# SCH_ESP_Hisense_485_2022-09-16.net
KiCad netlist of a schematic drawn in EasyEDA
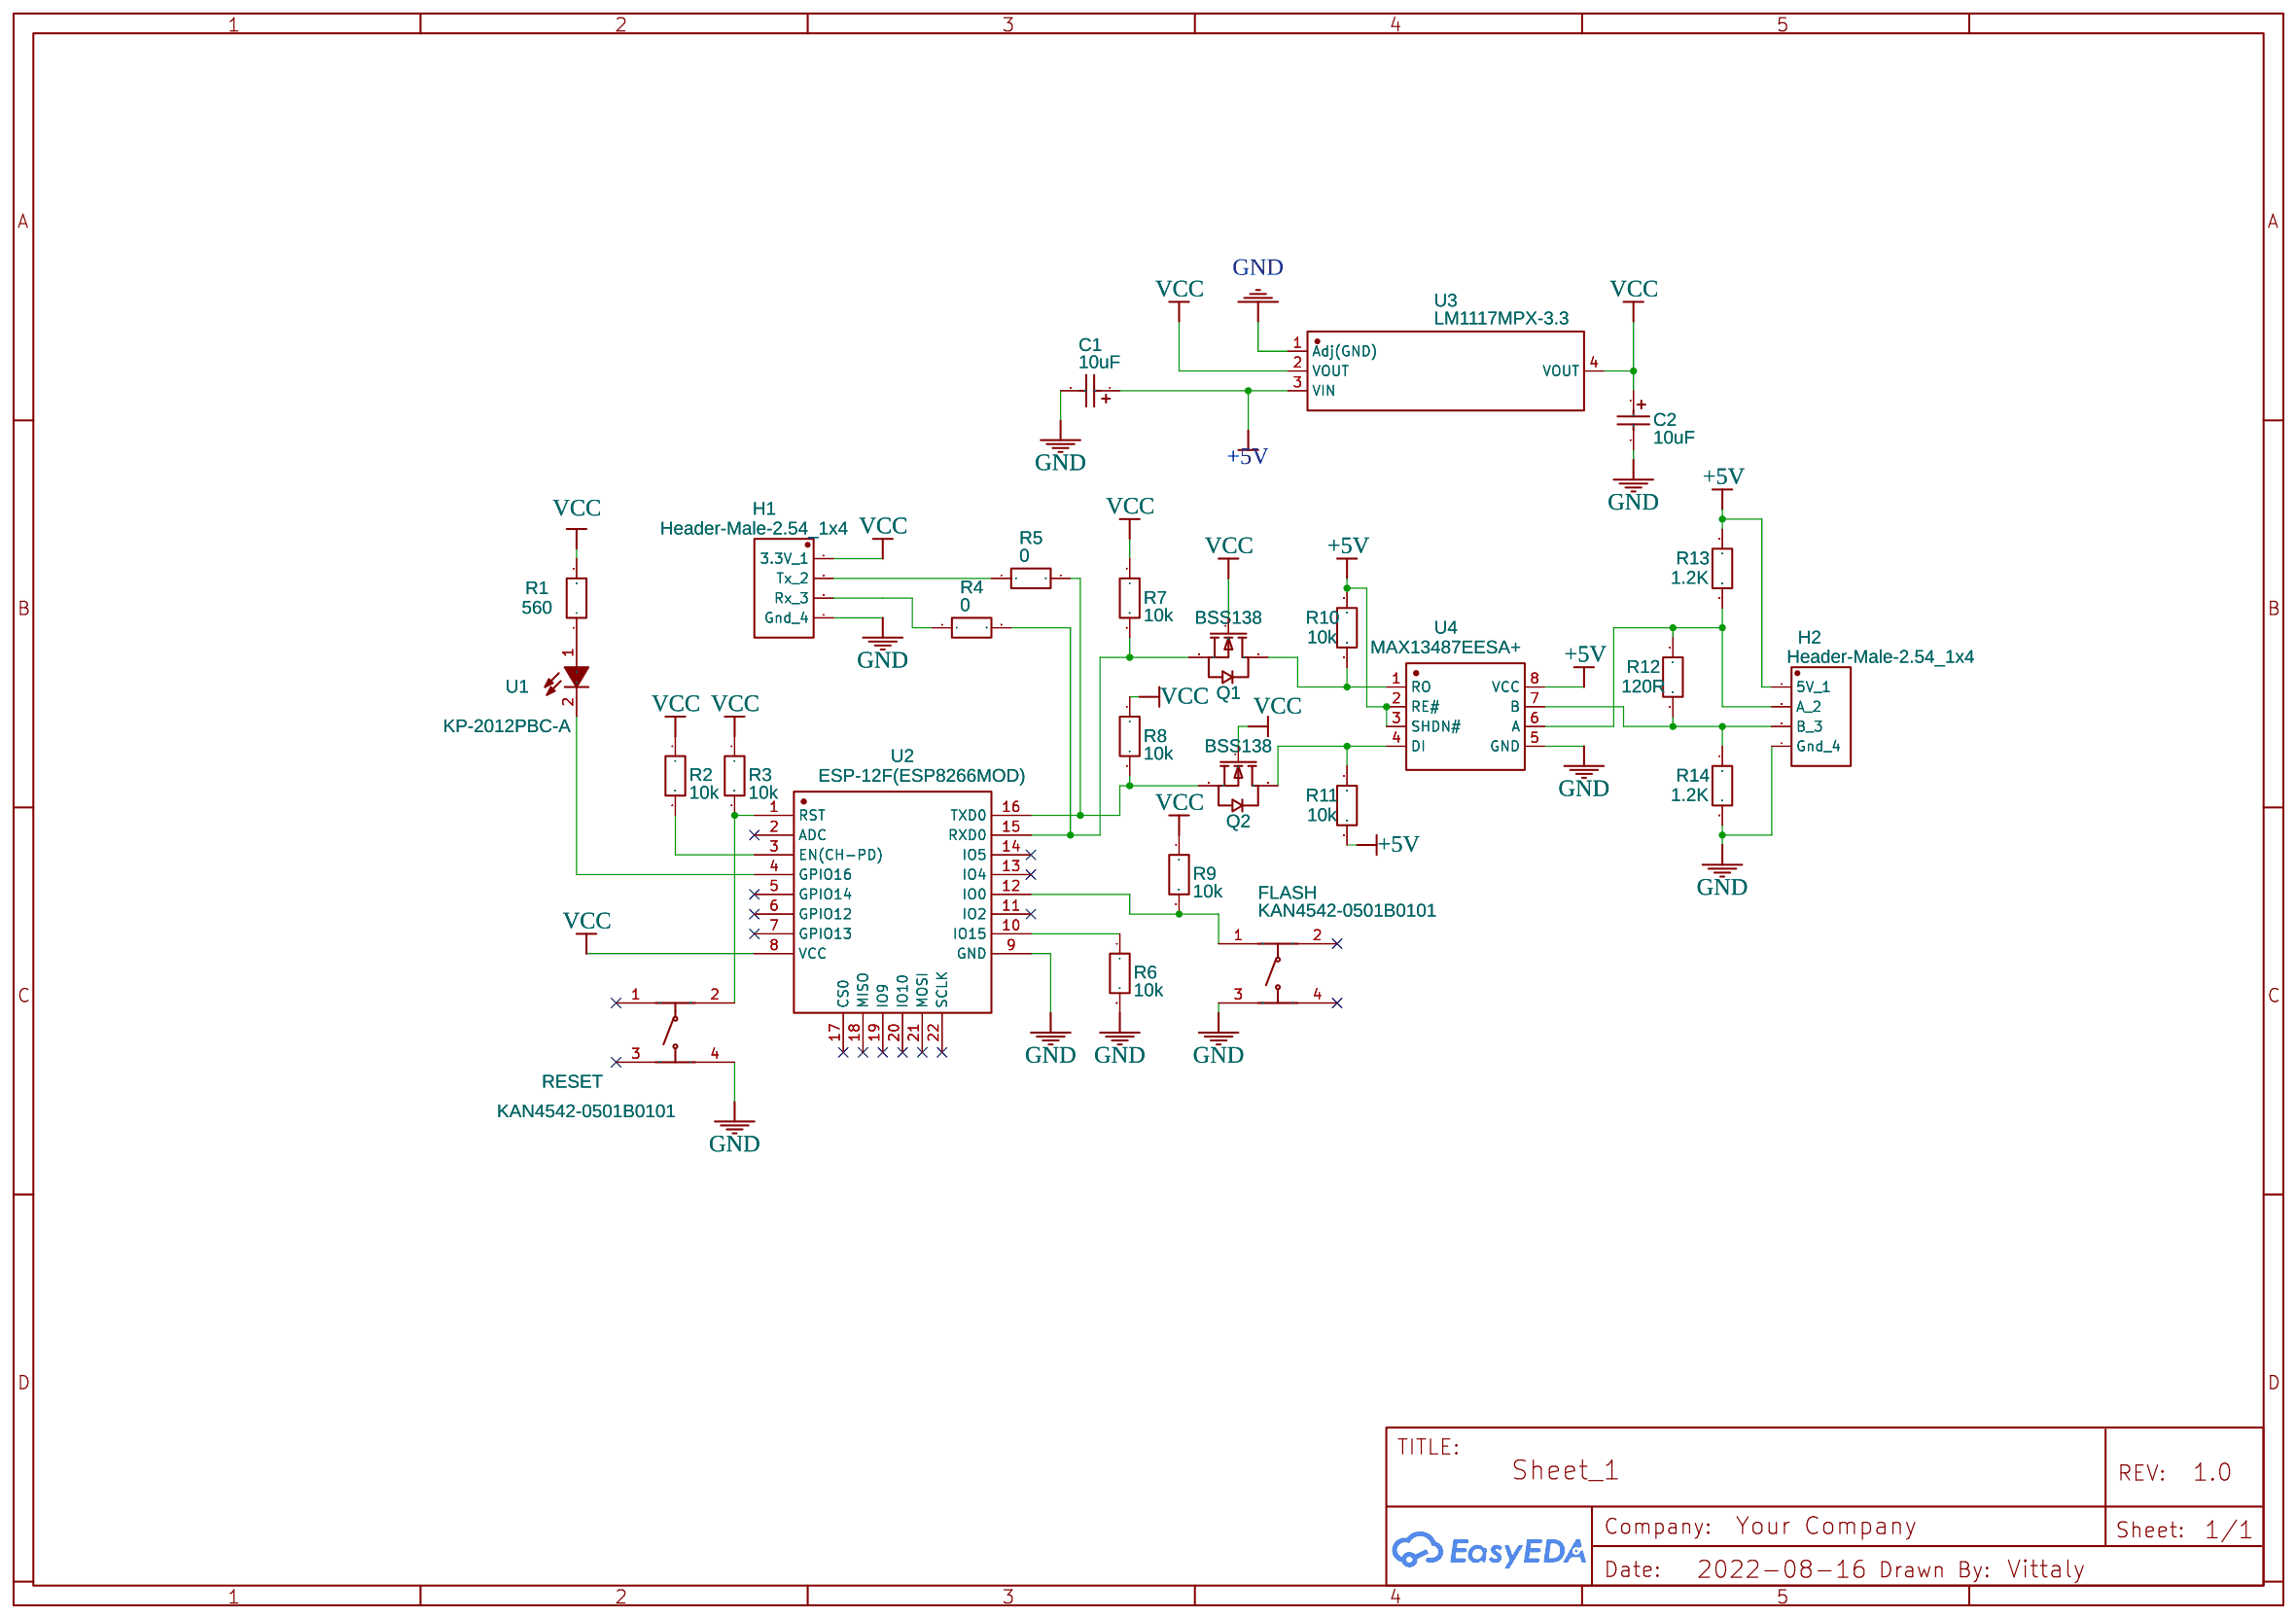
[diagram p0: schematic sheet]

(export (version "E")
  (design (tool "Eeschema 10.0.6"))
  (components
    (comp (ref "C1")
      (value "10uF")
      (fields
        (field (name "BOM_Manufacturer Part") "TAJB106M016RNJ")
        (field (name "BOM_Supplier Part") "C8016")
      )
      (libsource (lib "") (part "TAJB106M016RNJ"))
    )
    (comp (ref "C2")
      (value "10uF")
      (fields
        (field (name "BOM_Manufacturer Part") "TAJB106M016RNJ")
        (field (name "BOM_Supplier Part") "C8016")
      )
      (libsource (lib "") (part "TAJB106M016RNJ_1"))
    )
    (comp (ref "FLASH")
      (value "KAN4542-0501B0101")
      (fields (field (name "BOM_Supplier Part") "C2831431"))
      (libsource (lib "") (part "KAN4542-0501B0101_1"))
    )
    (comp (ref "H1")
      (value "Header-Male-2.54_1x4")
      (fields
        (field (name "BOM_Manufacturer Part") "210S-1*4P L=11.6MMGold-plated black")
        (field (name "BOM_Supplier Part") "C124378")
      )
      (libsource (lib "") (part "Header-Male-2.54_1x4"))
    )
    (comp (ref "H2")
      (value "Header-Male-2.54_1x4")
      (fields
        (field (name "BOM_Manufacturer Part") "210S-1*4P L=11.6MMGold-plated black")
        (field (name "BOM_Supplier Part") "C124378")
      )
      (libsource (lib "") (part "Header-Male-2.54_1x4_1"))
    )
    (comp (ref "Q1")
      (value "BSS138")
      (fields (field (name "BOM_Supplier Part") "C2681829"))
      (libsource (lib "") (part "BSS138_C2681829"))
    )
    (comp (ref "Q2")
      (value "BSS138")
      (fields (field (name "BOM_Supplier Part") "C2681829"))
      (libsource (lib "") (part "BSS138_C2681829"))
    )
    (comp (ref "R1") (value "560") (libsource (lib "") (part "R_1206_EU_2")))
    (comp (ref "R2") (value "10k") (libsource (lib "") (part "R_1206_EU")))
    (comp (ref "R3") (value "10k") (libsource (lib "") (part "R_1206_EU")))
    (comp (ref "R4")
      (value "0")
      (fields
        (field (name "BOM_Manufacturer Part") "AC1206JR-071KL")
        (field (name "BOM_Supplier Part") "C138242")
      )
      (libsource (lib "") (part "R_1206_EU_1"))
    )
    (comp (ref "R5")
      (value "0")
      (fields
        (field (name "BOM_Manufacturer Part") "AC1206JR-071KL")
        (field (name "BOM_Supplier Part") "C138242")
      )
      (libsource (lib "") (part "R_1206_EU_1"))
    )
    (comp (ref "R6") (value "10k") (libsource (lib "") (part "R_1206_EU")))
    (comp (ref "R7")
      (value "10k")
      (fields
        (field (name "BOM_Manufacturer Part") "AC1206JR-071KL")
        (field (name "BOM_Supplier Part") "C138242")
      )
      (libsource (lib "") (part "R_1206_EU"))
    )
    (comp (ref "R8")
      (value "10k")
      (fields
        (field (name "BOM_Manufacturer Part") "AC1206JR-071KL")
        (field (name "BOM_Supplier Part") "C138242")
      )
      (libsource (lib "") (part "R_1206_EU"))
    )
    (comp (ref "R9") (value "10k") (libsource (lib "") (part "R_1206_EU")))
    (comp (ref "R10")
      (value "10k")
      (fields
        (field (name "BOM_Manufacturer Part") "AC1206JR-071KL")
        (field (name "BOM_Supplier Part") "C138242")
      )
      (libsource (lib "") (part "R_1206_EU"))
    )
    (comp (ref "R11")
      (value "10k")
      (fields
        (field (name "BOM_Manufacturer Part") "AC1206JR-071KL")
        (field (name "BOM_Supplier Part") "C138242")
      )
      (libsource (lib "") (part "R_1206_EU"))
    )
    (comp (ref "R12")
      (value "120R")
      (fields
        (field (name "BOM_Manufacturer Part") "AC1206JR-071KL")
        (field (name "BOM_Supplier Part") "C138242")
      )
      (libsource (lib "") (part "R_1206_EU"))
    )
    (comp (ref "R13")
      (value "1.2K")
      (fields
        (field (name "BOM_Manufacturer Part") "AC1206JR-071KL")
        (field (name "BOM_Supplier Part") "C138242")
      )
      (libsource (lib "") (part "R_1206_EU"))
    )
    (comp (ref "R14")
      (value "1.2K")
      (fields
        (field (name "BOM_Manufacturer Part") "AC1206JR-071KL")
        (field (name "BOM_Supplier Part") "C138242")
      )
      (libsource (lib "") (part "R_1206_EU"))
    )
    (comp (ref "RESET")
      (value "KAN4542-0501B0101")
      (fields (field (name "BOM_Supplier Part") "C2831431"))
      (libsource (lib "") (part "KAN4542-0501B0101"))
    )
    (comp (ref "U1")
      (value "KP-2012PBC-A")
      (fields (field (name "BOM_Supplier Part") "C598276"))
      (libsource (lib "") (part "KP-2012PBC-A"))
    )
    (comp (ref "U2")
      (value "ESP-12F(ESP8266MOD)")
      (fields (field (name "BOM_Supplier Part") "C82891"))
      (libsource (lib "") (part "ESP-12F(ESP8266MOD)"))
    )
    (comp (ref "U3")
      (value "LM1117MPX-3.3")
      (fields
        (field (name "BOM_Manufacturer Part") "LM1117MPX-ADJ/NOPB")
        (field (name "BOM_Supplier Part") "C263277")
      )
      (libsource (lib "") (part "LM1117MPX-ADJ/NOPB"))
    )
    (comp (ref "U4")
      (value "MAX13487EESA+")
      (fields (field (name "BOM_Supplier Part") "C143342"))
      (libsource (lib "") (part "MAX13487EESA+"))
    )
  )
  (nets
    (net (code "1") (name "+5V") (class "Default")
      (node (ref "C1") (pin "1") (pinfunction "1_1") (pintype "input"))
      (node (ref "H2") (pin "1") (pinfunction "5V_1_1") (pintype "unspecified"))
      (node (ref "R10") (pin "1") (pinfunction "1_1") (pintype "unspecified"))
      (node (ref "R11") (pin "2") (pinfunction "2_2") (pintype "unspecified"))
      (node (ref "R13") (pin "1") (pinfunction "1_1") (pintype "unspecified"))
      (node (ref "U3") (pin "3") (pinfunction "VIN_3") (pintype "unspecified"))
      (node (ref "U4") (pin "2") (pinfunction "RE#_2") (pintype "unspecified"))
      (node (ref "U4") (pin "3") (pinfunction "SHDN#_3") (pintype "unspecified"))
      (node (ref "U4") (pin "8") (pinfunction "VCC_8") (pintype "unspecified"))
    )
    (net (code "2") (name "GND") (class "Default")
      (node (ref "C1") (pin "2") (pinfunction "2_2") (pintype "input"))
      (node (ref "C2") (pin "2") (pinfunction "2_2") (pintype "input"))
      (node (ref "FLASH") (pin "3") (pinfunction "3_3") (pintype "unspecified"))
      (node (ref "H1") (pin "4") (pinfunction "Gnd_4_4") (pintype "unspecified"))
      (node (ref "H2") (pin "4") (pinfunction "Gnd_4_4") (pintype "unspecified"))
      (node (ref "R14") (pin "2") (pinfunction "2_2") (pintype "unspecified"))
      (node (ref "R6") (pin "2") (pinfunction "2_2") (pintype "unspecified"))
      (node (ref "RESET") (pin "4") (pinfunction "4_4") (pintype "unspecified"))
      (node (ref "U2") (pin "9") (pinfunction "GND_9") (pintype "unspecified"))
      (node (ref "U3") (pin "1") (pinfunction "Adj(GND)_1") (pintype "unspecified"))
      (node (ref "U4") (pin "5") (pinfunction "GND_5") (pintype "unspecified"))
    )
    (net (code "3") (name "Net-(H1-Rx_3)") (class "Default")
      (node (ref "H1") (pin "3") (pinfunction "Rx_3_3") (pintype "unspecified"))
      (node (ref "R4") (pin "1") (pinfunction "1_1") (pintype "unspecified"))
    )
    (net (code "4") (name "Net-(H1-Tx_2)") (class "Default")
      (node (ref "H1") (pin "2") (pinfunction "Tx_2_2") (pintype "unspecified"))
      (node (ref "R5") (pin "1") (pinfunction "1_1") (pintype "unspecified"))
    )
    (net (code "5") (name "Net-(H2-A_2)") (class "Default")
      (node (ref "H2") (pin "2") (pinfunction "A_2_2") (pintype "unspecified"))
      (node (ref "R12") (pin "1") (pinfunction "1_1") (pintype "unspecified"))
      (node (ref "R13") (pin "2") (pinfunction "2_2") (pintype "unspecified"))
      (node (ref "U4") (pin "6") (pinfunction "A_6") (pintype "unspecified"))
    )
    (net (code "6") (name "Net-(H2-B_3)") (class "Default")
      (node (ref "H2") (pin "3") (pinfunction "B_3_3") (pintype "unspecified"))
      (node (ref "R12") (pin "2") (pinfunction "2_2") (pintype "unspecified"))
      (node (ref "R14") (pin "1") (pinfunction "1_1") (pintype "unspecified"))
      (node (ref "U4") (pin "7") (pinfunction "B_7") (pintype "unspecified"))
    )
    (net (code "7") (name "Net-(Q1-D)") (class "Default")
      (node (ref "Q1") (pin "3") (pinfunction "D_3") (pintype "unspecified"))
      (node (ref "R10") (pin "2") (pinfunction "2_2") (pintype "unspecified"))
      (node (ref "U4") (pin "1") (pinfunction "RO_1") (pintype "unspecified"))
    )
    (net (code "8") (name "Net-(Q1-S)") (class "Default")
      (node (ref "Q1") (pin "2") (pinfunction "S_2") (pintype "unspecified"))
      (node (ref "R4") (pin "2") (pinfunction "2_2") (pintype "unspecified"))
      (node (ref "R7") (pin "2") (pinfunction "2_2") (pintype "unspecified"))
      (node (ref "U2") (pin "15") (pinfunction "RXD0_15") (pintype "unspecified"))
    )
    (net (code "9") (name "Net-(Q2-D)") (class "Default")
      (node (ref "Q2") (pin "3") (pinfunction "D_3") (pintype "unspecified"))
      (node (ref "R11") (pin "1") (pinfunction "1_1") (pintype "unspecified"))
      (node (ref "U4") (pin "4") (pinfunction "DI_4") (pintype "unspecified"))
    )
    (net (code "10") (name "Net-(Q2-S)") (class "Default")
      (node (ref "Q2") (pin "2") (pinfunction "S_2") (pintype "unspecified"))
      (node (ref "R5") (pin "2") (pinfunction "2_2") (pintype "unspecified"))
      (node (ref "R8") (pin "2") (pinfunction "2_2") (pintype "unspecified"))
      (node (ref "U2") (pin "16") (pinfunction "TXD0_16") (pintype "unspecified"))
    )
    (net (code "11") (name "Net-(U1-A)") (class "Default")
      (node (ref "R1") (pin "1") (pinfunction "1_1") (pintype "unspecified"))
      (node (ref "U1") (pin "1") (pinfunction "A_1") (pintype "input"))
    )
    (net (code "12") (name "Net-(U1-C)") (class "Default")
      (node (ref "U1") (pin "2") (pinfunction "C_2") (pintype "input"))
      (node (ref "U2") (pin "4") (pinfunction "GPIO16_4") (pintype "unspecified"))
    )
    (net (code "13") (name "Net-(U2-EN(CH-PD))") (class "Default")
      (node (ref "R2") (pin "2") (pinfunction "2_2") (pintype "unspecified"))
      (node (ref "U2") (pin "3") (pinfunction "EN(CH-PD)_3") (pintype "unspecified"))
    )
    (net (code "14") (name "Net-(U2-IO0)") (class "Default")
      (node (ref "FLASH") (pin "1") (pinfunction "1_1") (pintype "unspecified"))
      (node (ref "R9") (pin "2") (pinfunction "2_2") (pintype "unspecified"))
      (node (ref "U2") (pin "12") (pinfunction "IO0_12") (pintype "unspecified"))
    )
    (net (code "15") (name "Net-(U2-IO15)") (class "Default")
      (node (ref "R6") (pin "1") (pinfunction "1_1") (pintype "unspecified"))
      (node (ref "U2") (pin "10") (pinfunction "IO15_10") (pintype "unspecified"))
    )
    (net (code "16") (name "Net-(U2-RST)") (class "Default")
      (node (ref "R3") (pin "2") (pinfunction "2_2") (pintype "unspecified"))
      (node (ref "RESET") (pin "2") (pinfunction "2_2") (pintype "unspecified"))
      (node (ref "U2") (pin "1") (pinfunction "RST_1") (pintype "unspecified"))
    )
    (net (code "17") (name "VCC") (class "Default")
      (node (ref "C2") (pin "1") (pinfunction "1_1") (pintype "input"))
      (node (ref "H1") (pin "1") (pinfunction "3.3V_1_1") (pintype "unspecified"))
      (node (ref "Q1") (pin "1") (pinfunction "G_1") (pintype "unspecified"))
      (node (ref "Q2") (pin "1") (pinfunction "G_1") (pintype "unspecified"))
      (node (ref "R1") (pin "2") (pinfunction "2_2") (pintype "unspecified"))
      (node (ref "R2") (pin "1") (pinfunction "1_1") (pintype "unspecified"))
      (node (ref "R3") (pin "1") (pinfunction "1_1") (pintype "unspecified"))
      (node (ref "R7") (pin "1") (pinfunction "1_1") (pintype "unspecified"))
      (node (ref "R8") (pin "1") (pinfunction "1_1") (pintype "unspecified"))
      (node (ref "R9") (pin "1") (pinfunction "1_1") (pintype "unspecified"))
      (node (ref "U2") (pin "8") (pinfunction "VCC_8") (pintype "unspecified"))
      (node (ref "U3") (pin "2") (pinfunction "VOUT_2") (pintype "unspecified"))
      (node (ref "U3") (pin "4") (pinfunction "VOUT_4") (pintype "unspecified"))
    )
    (net (code "18") (name "unconnected-(FLASH-Pad2)") (class "Default")
      (node (ref "FLASH") (pin "2") (pinfunction "2_2") (pintype "unspecified+no_connect"))
    )
    (net (code "19") (name "unconnected-(FLASH-Pad4)") (class "Default")
      (node (ref "FLASH") (pin "4") (pinfunction "4_4") (pintype "unspecified+no_connect"))
    )
    (net (code "20") (name "unconnected-(RESET-Pad1)") (class "Default")
      (node (ref "RESET") (pin "1") (pinfunction "1_1") (pintype "unspecified+no_connect"))
    )
    (net (code "21") (name "unconnected-(RESET-Pad3)") (class "Default")
      (node (ref "RESET") (pin "3") (pinfunction "3_3") (pintype "unspecified+no_connect"))
    )
    (net (code "22") (name "unconnected-(U2-ADC-Pad2)") (class "Default")
      (node (ref "U2") (pin "2") (pinfunction "ADC_2") (pintype "unspecified+no_connect"))
    )
    (net (code "23") (name "unconnected-(U2-CS0-Pad17)") (class "Default")
      (node (ref "U2") (pin "17") (pinfunction "CS0_17") (pintype "unspecified+no_connect"))
    )
    (net (code "24") (name "unconnected-(U2-GPIO12-Pad6)") (class "Default")
      (node (ref "U2") (pin "6") (pinfunction "GPIO12_6") (pintype "unspecified+no_connect"))
    )
    (net (code "25") (name "unconnected-(U2-GPIO13-Pad7)") (class "Default")
      (node (ref "U2") (pin "7") (pinfunction "GPIO13_7") (pintype "unspecified+no_connect"))
    )
    (net (code "26") (name "unconnected-(U2-GPIO14-Pad5)") (class "Default")
      (node (ref "U2") (pin "5") (pinfunction "GPIO14_5") (pintype "unspecified+no_connect"))
    )
    (net (code "27") (name "unconnected-(U2-IO2-Pad11)") (class "Default")
      (node (ref "U2") (pin "11") (pinfunction "IO2_11") (pintype "unspecified+no_connect"))
    )
    (net (code "28") (name "unconnected-(U2-IO4-Pad13)") (class "Default")
      (node (ref "U2") (pin "13") (pinfunction "IO4_13") (pintype "unspecified+no_connect"))
    )
    (net (code "29") (name "unconnected-(U2-IO5-Pad14)") (class "Default")
      (node (ref "U2") (pin "14") (pinfunction "IO5_14") (pintype "unspecified+no_connect"))
    )
    (net (code "30") (name "unconnected-(U2-IO9-Pad19)") (class "Default")
      (node (ref "U2") (pin "19") (pinfunction "IO9_19") (pintype "unspecified+no_connect"))
    )
    (net (code "31") (name "unconnected-(U2-IO10-Pad20)") (class "Default")
      (node (ref "U2") (pin "20") (pinfunction "IO10_20") (pintype "unspecified+no_connect"))
    )
    (net (code "32") (name "unconnected-(U2-MISO-Pad18)") (class "Default")
      (node (ref "U2") (pin "18") (pinfunction "MISO_18") (pintype "unspecified+no_connect"))
    )
    (net (code "33") (name "unconnected-(U2-MOSI-Pad21)") (class "Default")
      (node (ref "U2") (pin "21") (pinfunction "MOSI_21") (pintype "unspecified+no_connect"))
    )
    (net (code "34") (name "unconnected-(U2-SCLK-Pad22)") (class "Default")
      (node (ref "U2") (pin "22") (pinfunction "SCLK_22") (pintype "unspecified+no_connect"))
    )
  )
)
